# untitled.net
KiCad netlist of a schematic drawn in EAGLE
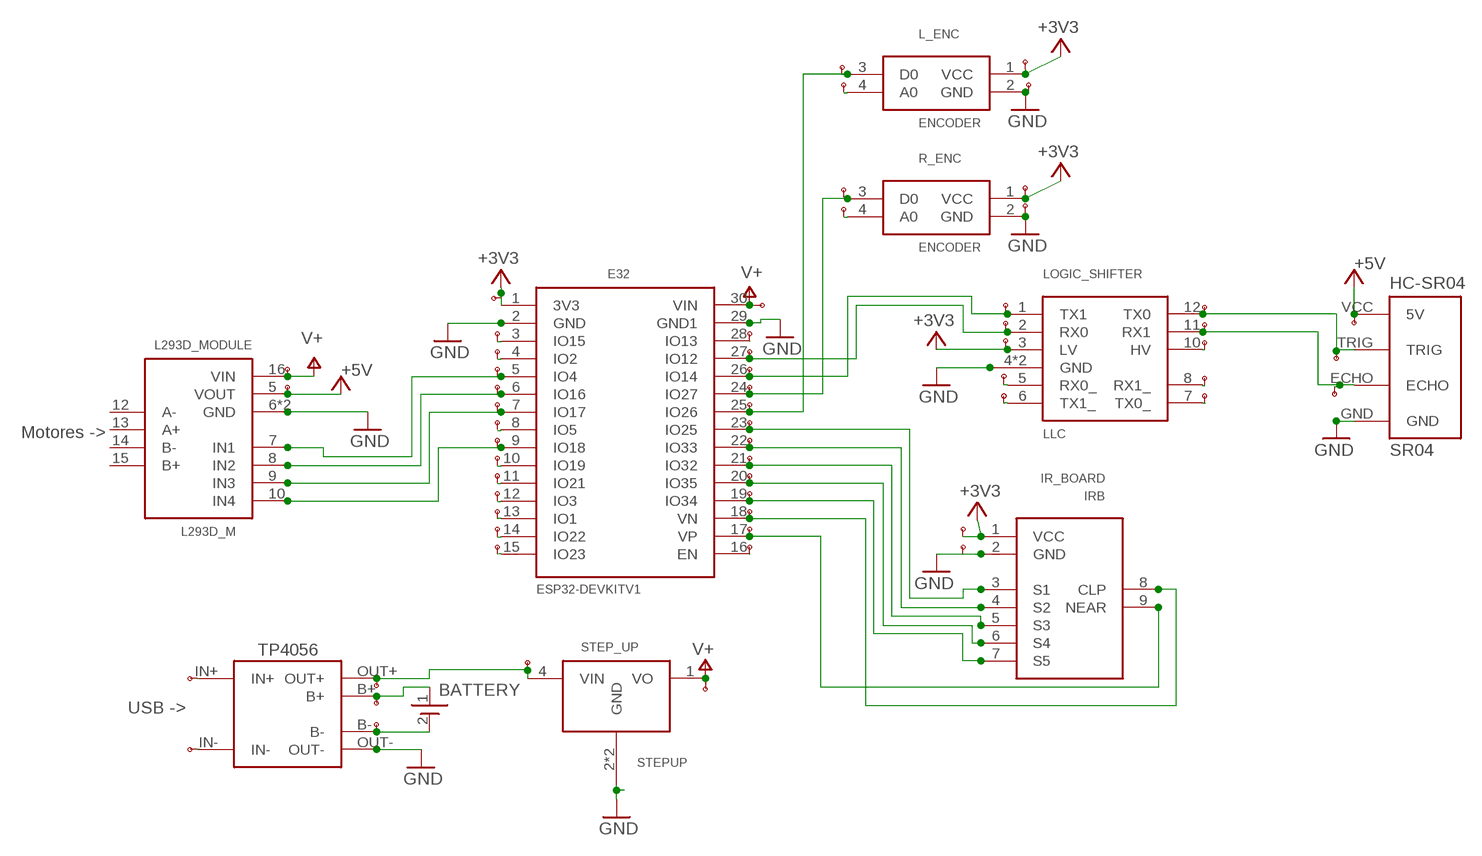
[diagram p0: schematic, sheet 1]

(export (version "E")
  (design (tool "Eeschema 10.0.6"))
  (components
    (comp (ref "BATTERY")
      (value "BAT_PAD")
      (footprint "eagle-import:BAT_PAD")
      (libsource (lib "eagle-import") (part "BAT_PAD"))
    )
    (comp (ref "BAT_CHARGER")
      (value "TP4056-MODULE")
      (footprint "eagle-import:TP4056-LITHIUM-PROTECTED-MODULE")
      (libsource (lib "eagle-import") (part "TP4056-MODULE"))
    )
    (comp (ref "E32")
      (value "ESP32DEVKITV1")
      (footprint "eagle-import:ESP32-DEVKITV1")
      (libsource (lib "eagle-import") (part "ESP32DEVKITV1"))
    )
    (comp (ref "IR_BOARD")
      (value "IRB")
      (footprint "eagle-import:IRB")
      (libsource (lib "eagle-import") (part "IRB"))
    )
    (comp (ref "L293D_MODULE")
      (value "L293D_M")
      (footprint "eagle-import:L293D_M")
      (libsource (lib "eagle-import") (part "L293D_M"))
    )
    (comp (ref "LOGIC_SHIFTER")
      (value "LLC")
      (footprint "eagle-import:LLC")
      (libsource (lib "eagle-import") (part "LLC"))
    )
    (comp (ref "L_ENC")
      (value "ENCODER")
      (footprint "eagle-import:ENCODER")
      (libsource (lib "eagle-import") (part "ENCODER"))
    )
    (comp (ref "R_ENC")
      (value "ENCODER")
      (footprint "eagle-import:ENCODER")
      (libsource (lib "eagle-import") (part "ENCODER"))
    )
    (comp (ref "SR04")
      (value "HC-SR04")
      (footprint "eagle-import:HC-SR04_FOOTPRINT")
      (libsource (lib "eagle-import") (part "HC-SR04"))
    )
    (comp (ref "STEP_UP")
      (value "STEPUP")
      (footprint "eagle-import:STEPUP")
      (libsource (lib "eagle-import") (part "STEPUP"))
    )
    (comp (ref "U$1") (value "TP") (footprint "eagle-import:TP") (libsource (lib "eagle-import") (part "TP")))
    (comp (ref "U$2") (value "TP") (footprint "eagle-import:TP") (libsource (lib "eagle-import") (part "TP")))
    (comp (ref "U$3") (value "TP") (footprint "eagle-import:TP") (libsource (lib "eagle-import") (part "TP")))
    (comp (ref "U$4") (value "TP") (footprint "eagle-import:TP") (libsource (lib "eagle-import") (part "TP")))
    (comp (ref "U$8") (value "TP") (footprint "eagle-import:TP") (libsource (lib "eagle-import") (part "TP")))
    (comp (ref "U$10")
      (value "TP")
      (footprint "eagle-import:TP")
      (libsource (lib "eagle-import") (part "TP"))
    )
    (comp (ref "U$11")
      (value "TP")
      (footprint "eagle-import:TP")
      (libsource (lib "eagle-import") (part "TP"))
    )
    (comp (ref "U$12")
      (value "TP")
      (footprint "eagle-import:TP")
      (libsource (lib "eagle-import") (part "TP"))
    )
    (comp (ref "U$13")
      (value "TP")
      (footprint "eagle-import:TP")
      (libsource (lib "eagle-import") (part "TP"))
    )
    (comp (ref "U$14")
      (value "TP")
      (footprint "eagle-import:TP")
      (libsource (lib "eagle-import") (part "TP"))
    )
    (comp (ref "U$15")
      (value "TP")
      (footprint "eagle-import:TP")
      (libsource (lib "eagle-import") (part "TP"))
    )
    (comp (ref "U$16")
      (value "TP")
      (footprint "eagle-import:TP")
      (libsource (lib "eagle-import") (part "TP"))
    )
    (comp (ref "U$17")
      (value "TP")
      (footprint "eagle-import:TP")
      (libsource (lib "eagle-import") (part "TP"))
    )
    (comp (ref "U$18")
      (value "TP")
      (footprint "eagle-import:TP")
      (libsource (lib "eagle-import") (part "TP"))
    )
    (comp (ref "U$19")
      (value "TP")
      (footprint "eagle-import:TP")
      (libsource (lib "eagle-import") (part "TP"))
    )
    (comp (ref "U$20")
      (value "TP")
      (footprint "eagle-import:TP")
      (libsource (lib "eagle-import") (part "TP"))
    )
    (comp (ref "U$21")
      (value "TP")
      (footprint "eagle-import:TP")
      (libsource (lib "eagle-import") (part "TP"))
    )
    (comp (ref "U$22")
      (value "TP")
      (footprint "eagle-import:TP")
      (libsource (lib "eagle-import") (part "TP"))
    )
    (comp (ref "U$23")
      (value "TP")
      (footprint "eagle-import:TP")
      (libsource (lib "eagle-import") (part "TP"))
    )
    (comp (ref "U$24")
      (value "TP")
      (footprint "eagle-import:TP")
      (libsource (lib "eagle-import") (part "TP"))
    )
    (comp (ref "U$25")
      (value "TP")
      (footprint "eagle-import:TP")
      (libsource (lib "eagle-import") (part "TP"))
    )
    (comp (ref "U$26")
      (value "TP")
      (footprint "eagle-import:TP")
      (libsource (lib "eagle-import") (part "TP"))
    )
    (comp (ref "U$27")
      (value "TP")
      (footprint "eagle-import:TP")
      (libsource (lib "eagle-import") (part "TP"))
    )
    (comp (ref "U$28")
      (value "TP")
      (footprint "eagle-import:TP")
      (libsource (lib "eagle-import") (part "TP"))
    )
    (comp (ref "U$29")
      (value "TP")
      (footprint "eagle-import:TP")
      (libsource (lib "eagle-import") (part "TP"))
    )
    (comp (ref "U$30")
      (value "TP")
      (footprint "eagle-import:TP")
      (libsource (lib "eagle-import") (part "TP"))
    )
    (comp (ref "U$31")
      (value "TP")
      (footprint "eagle-import:TP")
      (libsource (lib "eagle-import") (part "TP"))
    )
    (comp (ref "U$32")
      (value "TP")
      (footprint "eagle-import:TP")
      (libsource (lib "eagle-import") (part "TP"))
    )
    (comp (ref "U$33")
      (value "TP")
      (footprint "eagle-import:TP")
      (libsource (lib "eagle-import") (part "TP"))
    )
    (comp (ref "U$34")
      (value "TP")
      (footprint "eagle-import:TP")
      (libsource (lib "eagle-import") (part "TP"))
    )
    (comp (ref "U$36")
      (value "TP")
      (footprint "eagle-import:TP")
      (libsource (lib "eagle-import") (part "TP"))
    )
    (comp (ref "U$37")
      (value "TP")
      (footprint "eagle-import:TP")
      (libsource (lib "eagle-import") (part "TP"))
    )
    (comp (ref "U$38")
      (value "TP")
      (footprint "eagle-import:TP")
      (libsource (lib "eagle-import") (part "TP"))
    )
    (comp (ref "U$40")
      (value "TP")
      (footprint "eagle-import:TP")
      (libsource (lib "eagle-import") (part "TP"))
    )
    (comp (ref "U$41")
      (value "TP")
      (footprint "eagle-import:TP")
      (libsource (lib "eagle-import") (part "TP"))
    )
    (comp (ref "U$42")
      (value "TP")
      (footprint "eagle-import:TP")
      (libsource (lib "eagle-import") (part "TP"))
    )
    (comp (ref "U$43")
      (value "TP")
      (footprint "eagle-import:TP")
      (libsource (lib "eagle-import") (part "TP"))
    )
    (comp (ref "U$44")
      (value "TP")
      (footprint "eagle-import:TP")
      (libsource (lib "eagle-import") (part "TP"))
    )
    (comp (ref "U$46")
      (value "TP")
      (footprint "eagle-import:TP")
      (libsource (lib "eagle-import") (part "TP"))
    )
    (comp (ref "U$47")
      (value "TP")
      (footprint "eagle-import:TP")
      (libsource (lib "eagle-import") (part "TP"))
    )
    (comp (ref "U$48")
      (value "TP")
      (footprint "eagle-import:TP")
      (libsource (lib "eagle-import") (part "TP"))
    )
    (comp (ref "U$49")
      (value "TP")
      (footprint "eagle-import:TP")
      (libsource (lib "eagle-import") (part "TP"))
    )
    (comp (ref "U$50")
      (value "TP")
      (footprint "eagle-import:TP")
      (libsource (lib "eagle-import") (part "TP"))
    )
    (comp (ref "U$51")
      (value "TP")
      (footprint "eagle-import:TP")
      (libsource (lib "eagle-import") (part "TP"))
    )
    (comp (ref "U$52")
      (value "TP")
      (footprint "eagle-import:TP")
      (libsource (lib "eagle-import") (part "TP"))
    )
    (comp (ref "U$53")
      (value "TP")
      (footprint "eagle-import:TP")
      (libsource (lib "eagle-import") (part "TP"))
    )
    (comp (ref "U$54")
      (value "TP")
      (footprint "eagle-import:TP")
      (libsource (lib "eagle-import") (part "TP"))
    )
    (comp (ref "U$55")
      (value "TP")
      (footprint "eagle-import:TP")
      (libsource (lib "eagle-import") (part "TP"))
    )
    (comp (ref "U$56")
      (value "TP")
      (footprint "eagle-import:TP")
      (libsource (lib "eagle-import") (part "TP"))
    )
    (comp (ref "U$57")
      (value "TP")
      (footprint "eagle-import:TP")
      (libsource (lib "eagle-import") (part "TP"))
    )
    (comp (ref "U$59")
      (value "TP")
      (footprint "eagle-import:TP")
      (libsource (lib "eagle-import") (part "TP"))
    )
    (comp (ref "U$60")
      (value "TP")
      (footprint "eagle-import:TP")
      (libsource (lib "eagle-import") (part "TP"))
    )
    (comp (ref "U$61")
      (value "TP")
      (footprint "eagle-import:TP")
      (libsource (lib "eagle-import") (part "TP"))
    )
    (comp (ref "U$62")
      (value "TP")
      (footprint "eagle-import:TP")
      (libsource (lib "eagle-import") (part "TP"))
    )
    (comp (ref "U$63")
      (value "TP")
      (footprint "eagle-import:TP")
      (libsource (lib "eagle-import") (part "TP"))
    )
    (comp (ref "U$64")
      (value "TP")
      (footprint "eagle-import:TP")
      (libsource (lib "eagle-import") (part "TP"))
    )
    (comp (ref "U$65")
      (value "TP")
      (footprint "eagle-import:TP")
      (libsource (lib "eagle-import") (part "TP"))
    )
    (comp (ref "U$67")
      (value "TP")
      (footprint "eagle-import:TP")
      (libsource (lib "eagle-import") (part "TP"))
    )
    (comp (ref "U$68")
      (value "TP")
      (footprint "eagle-import:TP")
      (libsource (lib "eagle-import") (part "TP"))
    )
    (comp (ref "U$69")
      (value "TP")
      (footprint "eagle-import:TP")
      (libsource (lib "eagle-import") (part "TP"))
    )
  )
  (nets
    (net (code "1") (name "+3V3") (class "Default")
      (node (ref "E32") (pin "1") (pinfunction "3V3_1") (pintype "bidirectional"))
      (node (ref "IR_BOARD") (pin "1") (pinfunction "VCC_1") (pintype "bidirectional"))
      (node (ref "LOGIC_SHIFTER") (pin "3") (pinfunction "LV_3") (pintype "bidirectional"))
      (node (ref "L_ENC") (pin "1") (pinfunction "VCC_1") (pintype "bidirectional"))
      (node (ref "R_ENC") (pin "1") (pinfunction "VCC_1") (pintype "bidirectional"))
      (node (ref "U$3") (pin "P$1") (pinfunction "P$1_P$1") (pintype "bidirectional"))
      (node (ref "U$49") (pin "P$1") (pinfunction "P$1_P$1") (pintype "bidirectional"))
      (node (ref "U$51") (pin "P$1") (pinfunction "P$1_P$1") (pintype "bidirectional"))
      (node (ref "U$57") (pin "P$1") (pinfunction "P$1_P$1") (pintype "bidirectional"))
      (node (ref "U$8") (pin "P$1") (pinfunction "P$1_P$1") (pintype "bidirectional"))
    )
    (net (code "2") (name "+5V") (class "Default")
      (node (ref "L293D_MODULE") (pin "5") (pinfunction "VOUT_5") (pintype "output"))
      (node (ref "SR04") (pin "VCC") (pinfunction "5V_VCC") (pintype "bidirectional"))
      (node (ref "U$2") (pin "P$1") (pinfunction "P$1_P$1") (pintype "bidirectional"))
      (node (ref "U$69") (pin "P$1") (pinfunction "P$1_P$1") (pintype "bidirectional"))
    )
    (net (code "3") (name "GND") (class "Default")
      (node (ref "BAT_CHARGER") (pin "OUT-") (pinfunction "OUT-_OUT-") (pintype "power_in"))
      (node (ref "E32") (pin "2") (pinfunction "GND_2") (pintype "bidirectional"))
      (node (ref "E32") (pin "29") (pinfunction "GND1_29") (pintype "bidirectional"))
      (node (ref "IR_BOARD") (pin "2") (pinfunction "GND_2") (pintype "bidirectional"))
      (node (ref "L293D_MODULE") (pin "11") (pinfunction "GND_11") (pintype "bidirectional"))
      (node (ref "L293D_MODULE") (pin "6") (pinfunction "GND_6") (pintype "bidirectional"))
      (node (ref "LOGIC_SHIFTER") (pin "4") (pinfunction "GND_4") (pintype "bidirectional"))
      (node (ref "LOGIC_SHIFTER") (pin "9") (pinfunction "GND_9") (pintype "bidirectional"))
      (node (ref "L_ENC") (pin "2") (pinfunction "GND_2") (pintype "bidirectional"))
      (node (ref "R_ENC") (pin "2") (pinfunction "GND_2") (pintype "bidirectional"))
      (node (ref "SR04") (pin "GND") (pinfunction "GND_GND") (pintype "bidirectional"))
      (node (ref "STEP_UP") (pin "2") (pinfunction "GND_2") (pintype "bidirectional"))
      (node (ref "STEP_UP") (pin "3") (pinfunction "GND_3") (pintype "bidirectional"))
      (node (ref "U$4") (pin "P$1") (pinfunction "P$1_P$1") (pintype "bidirectional"))
      (node (ref "U$50") (pin "P$1") (pinfunction "P$1_P$1") (pintype "bidirectional"))
      (node (ref "U$52") (pin "P$1") (pinfunction "P$1_P$1") (pintype "bidirectional"))
    )
    (net (code "4") (name "Net-(BATTERY-+)") (class "Default")
      (node (ref "BATTERY") (pin "1") (pinfunction "+_1") (pintype "bidirectional"))
      (node (ref "BAT_CHARGER") (pin "B+") (pinfunction "B+_B+") (pintype "power_in"))
      (node (ref "U$41") (pin "P$1") (pinfunction "P$1_P$1") (pintype "bidirectional"))
    )
    (net (code "5") (name "Net-(BATTERY--)") (class "Default")
      (node (ref "BATTERY") (pin "2") (pinfunction "-_2") (pintype "bidirectional"))
      (node (ref "BAT_CHARGER") (pin "B-") (pinfunction "B-_B-") (pintype "power_in"))
      (node (ref "U$40") (pin "P$1") (pinfunction "P$1_P$1") (pintype "bidirectional"))
    )
    (net (code "6") (name "Net-(BAT_CHARGER-PadIN+)") (class "Default")
      (node (ref "BAT_CHARGER") (pin "IN+") (pinfunction "IN+_IN+") (pintype "power_in"))
      (node (ref "U$37") (pin "P$1") (pinfunction "P$1_P$1") (pintype "bidirectional"))
    )
    (net (code "7") (name "Net-(BAT_CHARGER-PadIN-)") (class "Default")
      (node (ref "BAT_CHARGER") (pin "IN-") (pinfunction "IN-_IN-") (pintype "power_in"))
      (node (ref "U$38") (pin "P$1") (pinfunction "P$1_P$1") (pintype "bidirectional"))
    )
    (net (code "8") (name "Net-(E32-EN)") (class "Default")
      (node (ref "E32") (pin "16") (pinfunction "EN_16") (pintype "bidirectional"))
      (node (ref "U$22") (pin "P$1") (pinfunction "P$1_P$1") (pintype "bidirectional"))
    )
    (net (code "9") (name "Net-(E32-IO1)") (class "Default")
      (node (ref "E32") (pin "13") (pinfunction "IO1_13") (pintype "bidirectional"))
      (node (ref "U$19") (pin "P$1") (pinfunction "P$1_P$1") (pintype "bidirectional"))
    )
    (net (code "10") (name "Net-(E32-IO2)") (class "Default")
      (node (ref "E32") (pin "4") (pinfunction "IO2_4") (pintype "bidirectional"))
      (node (ref "U$11") (pin "P$1") (pinfunction "P$1_P$1") (pintype "bidirectional"))
    )
    (net (code "11") (name "Net-(E32-IO3)") (class "Default")
      (node (ref "E32") (pin "12") (pinfunction "IO3_12") (pintype "bidirectional"))
      (node (ref "U$18") (pin "P$1") (pinfunction "P$1_P$1") (pintype "bidirectional"))
    )
    (net (code "12") (name "Net-(E32-IO4)") (class "Default")
      (node (ref "E32") (pin "5") (pinfunction "IO4_5") (pintype "bidirectional"))
      (node (ref "L293D_MODULE") (pin "7") (pinfunction "IN1_7") (pintype "input"))
      (node (ref "U$46") (pin "P$1") (pinfunction "P$1_P$1") (pintype "bidirectional"))
    )
    (net (code "13") (name "Net-(E32-IO5)") (class "Default")
      (node (ref "E32") (pin "8") (pinfunction "IO5_8") (pintype "bidirectional"))
      (node (ref "U$14") (pin "P$1") (pinfunction "P$1_P$1") (pintype "bidirectional"))
    )
    (net (code "14") (name "Net-(E32-IO12)") (class "Default")
      (node (ref "E32") (pin "27") (pinfunction "IO12_27") (pintype "bidirectional"))
      (node (ref "LOGIC_SHIFTER") (pin "2") (pinfunction "RX0_2") (pintype "bidirectional"))
      (node (ref "U$33") (pin "P$1") (pinfunction "P$1_P$1") (pintype "bidirectional"))
      (node (ref "U$56") (pin "P$1") (pinfunction "P$1_P$1") (pintype "bidirectional"))
    )
    (net (code "15") (name "Net-(E32-IO13)") (class "Default")
      (node (ref "E32") (pin "28") (pinfunction "IO13_28") (pintype "bidirectional"))
      (node (ref "U$34") (pin "P$1") (pinfunction "P$1_P$1") (pintype "bidirectional"))
    )
    (net (code "16") (name "Net-(E32-IO14)") (class "Default")
      (node (ref "E32") (pin "26") (pinfunction "IO14_26") (pintype "bidirectional"))
      (node (ref "LOGIC_SHIFTER") (pin "1") (pinfunction "TX1_1") (pintype "bidirectional"))
      (node (ref "U$32") (pin "P$1") (pinfunction "P$1_P$1") (pintype "bidirectional"))
      (node (ref "U$55") (pin "P$1") (pinfunction "P$1_P$1") (pintype "bidirectional"))
    )
    (net (code "17") (name "Net-(E32-IO15)") (class "Default")
      (node (ref "E32") (pin "3") (pinfunction "IO15_3") (pintype "bidirectional"))
      (node (ref "U$10") (pin "P$1") (pinfunction "P$1_P$1") (pintype "bidirectional"))
    )
    (net (code "18") (name "Net-(E32-IO16)") (class "Default")
      (node (ref "E32") (pin "6") (pinfunction "IO16_6") (pintype "bidirectional"))
      (node (ref "L293D_MODULE") (pin "8") (pinfunction "IN2_8") (pintype "input"))
      (node (ref "U$12") (pin "P$1") (pinfunction "P$1_P$1") (pintype "bidirectional"))
    )
    (net (code "19") (name "Net-(E32-IO17)") (class "Default")
      (node (ref "E32") (pin "7") (pinfunction "IO17_7") (pintype "bidirectional"))
      (node (ref "L293D_MODULE") (pin "9") (pinfunction "IN3_9") (pintype "input"))
      (node (ref "U$13") (pin "P$1") (pinfunction "P$1_P$1") (pintype "bidirectional"))
    )
    (net (code "20") (name "Net-(E32-IO18)") (class "Default")
      (node (ref "E32") (pin "9") (pinfunction "IO18_9") (pintype "bidirectional"))
      (node (ref "L293D_MODULE") (pin "10") (pinfunction "IN4_10") (pintype "input"))
      (node (ref "U$15") (pin "P$1") (pinfunction "P$1_P$1") (pintype "bidirectional"))
    )
    (net (code "21") (name "Net-(E32-IO19)") (class "Default")
      (node (ref "E32") (pin "10") (pinfunction "IO19_10") (pintype "bidirectional"))
      (node (ref "U$16") (pin "P$1") (pinfunction "P$1_P$1") (pintype "bidirectional"))
    )
    (net (code "22") (name "Net-(E32-IO21)") (class "Default")
      (node (ref "E32") (pin "11") (pinfunction "IO21_11") (pintype "bidirectional"))
      (node (ref "U$17") (pin "P$1") (pinfunction "P$1_P$1") (pintype "bidirectional"))
    )
    (net (code "23") (name "Net-(E32-IO22)") (class "Default")
      (node (ref "E32") (pin "14") (pinfunction "IO22_14") (pintype "bidirectional"))
      (node (ref "U$20") (pin "P$1") (pinfunction "P$1_P$1") (pintype "bidirectional"))
    )
    (net (code "24") (name "Net-(E32-IO23)") (class "Default")
      (node (ref "E32") (pin "15") (pinfunction "IO23_15") (pintype "bidirectional"))
      (node (ref "U$21") (pin "P$1") (pinfunction "P$1_P$1") (pintype "bidirectional"))
    )
    (net (code "25") (name "Net-(E32-IO25)") (class "Default")
      (node (ref "E32") (pin "23") (pinfunction "IO25_23") (pintype "bidirectional"))
      (node (ref "IR_BOARD") (pin "3") (pinfunction "S1_3") (pintype "bidirectional"))
      (node (ref "U$29") (pin "P$1") (pinfunction "P$1_P$1") (pintype "bidirectional"))
    )
    (net (code "26") (name "Net-(E32-IO26)") (class "Default")
      (node (ref "E32") (pin "25") (pinfunction "IO26_25") (pintype "bidirectional"))
      (node (ref "L_ENC") (pin "3") (pinfunction "D0_3") (pintype "bidirectional"))
      (node (ref "U$30") (pin "P$1") (pinfunction "P$1_P$1") (pintype "bidirectional"))
      (node (ref "U$47") (pin "P$1") (pinfunction "P$1_P$1") (pintype "bidirectional"))
    )
    (net (code "27") (name "Net-(E32-IO27)") (class "Default")
      (node (ref "E32") (pin "24") (pinfunction "IO27_24") (pintype "bidirectional"))
      (node (ref "R_ENC") (pin "3") (pinfunction "D0_3") (pintype "bidirectional"))
      (node (ref "U$31") (pin "P$1") (pinfunction "P$1_P$1") (pintype "bidirectional"))
      (node (ref "U$54") (pin "P$1") (pinfunction "P$1_P$1") (pintype "bidirectional"))
    )
    (net (code "28") (name "Net-(E32-IO32)") (class "Default")
      (node (ref "E32") (pin "21") (pinfunction "IO32_21") (pintype "bidirectional"))
      (node (ref "IR_BOARD") (pin "5") (pinfunction "S3_5") (pintype "bidirectional"))
      (node (ref "U$27") (pin "P$1") (pinfunction "P$1_P$1") (pintype "bidirectional"))
    )
    (net (code "29") (name "Net-(E32-IO33)") (class "Default")
      (node (ref "E32") (pin "22") (pinfunction "IO33_22") (pintype "bidirectional"))
      (node (ref "IR_BOARD") (pin "4") (pinfunction "S2_4") (pintype "bidirectional"))
      (node (ref "U$28") (pin "P$1") (pinfunction "P$1_P$1") (pintype "bidirectional"))
    )
    (net (code "30") (name "Net-(E32-IO34)") (class "Default")
      (node (ref "E32") (pin "19") (pinfunction "IO34_19") (pintype "bidirectional"))
      (node (ref "IR_BOARD") (pin "7") (pinfunction "S5_7") (pintype "bidirectional"))
      (node (ref "U$25") (pin "P$1") (pinfunction "P$1_P$1") (pintype "bidirectional"))
    )
    (net (code "31") (name "Net-(E32-IO35)") (class "Default")
      (node (ref "E32") (pin "20") (pinfunction "IO35_20") (pintype "bidirectional"))
      (node (ref "IR_BOARD") (pin "6") (pinfunction "S4_6") (pintype "bidirectional"))
      (node (ref "U$26") (pin "P$1") (pinfunction "P$1_P$1") (pintype "bidirectional"))
    )
    (net (code "32") (name "Net-(E32-VN)") (class "Default")
      (node (ref "E32") (pin "18") (pinfunction "VN_18") (pintype "bidirectional"))
      (node (ref "IR_BOARD") (pin "8") (pinfunction "CLP_8") (pintype "bidirectional"))
      (node (ref "U$24") (pin "P$1") (pinfunction "P$1_P$1") (pintype "bidirectional"))
    )
    (net (code "33") (name "Net-(E32-VP)") (class "Default")
      (node (ref "E32") (pin "17") (pinfunction "VP_17") (pintype "bidirectional"))
      (node (ref "IR_BOARD") (pin "9") (pinfunction "NEAR_9") (pintype "bidirectional"))
      (node (ref "U$23") (pin "P$1") (pinfunction "P$1_P$1") (pintype "bidirectional"))
    )
    (net (code "34") (name "Net-(LOGIC_SHIFTER-HV)") (class "Default")
      (node (ref "LOGIC_SHIFTER") (pin "10") (pinfunction "HV_10") (pintype "bidirectional"))
      (node (ref "U$63") (pin "P$1") (pinfunction "P$1_P$1") (pintype "bidirectional"))
    )
    (net (code "35") (name "Net-(LOGIC_SHIFTER-RX0_)") (class "Default")
      (node (ref "LOGIC_SHIFTER") (pin "5") (pinfunction "RX0__5") (pintype "bidirectional"))
      (node (ref "U$59") (pin "P$1") (pinfunction "P$1_P$1") (pintype "bidirectional"))
    )
    (net (code "36") (name "Net-(LOGIC_SHIFTER-RX1)") (class "Default")
      (node (ref "LOGIC_SHIFTER") (pin "11") (pinfunction "RX1_11") (pintype "bidirectional"))
      (node (ref "SR04") (pin "ECHO") (pinfunction "ECHO_ECHO") (pintype "bidirectional"))
      (node (ref "U$64") (pin "P$1") (pinfunction "P$1_P$1") (pintype "bidirectional"))
      (node (ref "U$67") (pin "P$1") (pinfunction "P$1_P$1") (pintype "bidirectional"))
    )
    (net (code "37") (name "Net-(LOGIC_SHIFTER-RX1_)") (class "Default")
      (node (ref "LOGIC_SHIFTER") (pin "8") (pinfunction "RX1__8") (pintype "bidirectional"))
      (node (ref "U$62") (pin "P$1") (pinfunction "P$1_P$1") (pintype "bidirectional"))
    )
    (net (code "38") (name "Net-(LOGIC_SHIFTER-TX0)") (class "Default")
      (node (ref "LOGIC_SHIFTER") (pin "12") (pinfunction "TX0_12") (pintype "bidirectional"))
      (node (ref "SR04") (pin "TRIG") (pinfunction "TRIG_TRIG") (pintype "bidirectional"))
      (node (ref "U$65") (pin "P$1") (pinfunction "P$1_P$1") (pintype "bidirectional"))
      (node (ref "U$68") (pin "P$1") (pinfunction "P$1_P$1") (pintype "bidirectional"))
    )
    (net (code "39") (name "Net-(LOGIC_SHIFTER-TX0_)") (class "Default")
      (node (ref "LOGIC_SHIFTER") (pin "7") (pinfunction "TX0__7") (pintype "bidirectional"))
      (node (ref "U$61") (pin "P$1") (pinfunction "P$1_P$1") (pintype "bidirectional"))
    )
    (net (code "40") (name "Net-(LOGIC_SHIFTER-TX1_)") (class "Default")
      (node (ref "LOGIC_SHIFTER") (pin "6") (pinfunction "TX1__6") (pintype "bidirectional"))
      (node (ref "U$60") (pin "P$1") (pinfunction "P$1_P$1") (pintype "bidirectional"))
    )
    (net (code "41") (name "Net-(L_ENC-A0)") (class "Default")
      (node (ref "L_ENC") (pin "4") (pinfunction "A0_4") (pintype "bidirectional"))
      (node (ref "U$48") (pin "P$1") (pinfunction "P$1_P$1") (pintype "bidirectional"))
    )
    (net (code "42") (name "Net-(R_ENC-A0)") (class "Default")
      (node (ref "R_ENC") (pin "4") (pinfunction "A0_4") (pintype "bidirectional"))
      (node (ref "U$53") (pin "P$1") (pinfunction "P$1_P$1") (pintype "bidirectional"))
    )
    (net (code "43") (name "Net-(STEP_UP-VIN)") (class "Default")
      (node (ref "BAT_CHARGER") (pin "OUT+") (pinfunction "OUT+_OUT+") (pintype "power_in"))
      (node (ref "STEP_UP") (pin "4") (pinfunction "VIN_4") (pintype "bidirectional"))
      (node (ref "U$42") (pin "P$1") (pinfunction "P$1_P$1") (pintype "bidirectional"))
      (node (ref "U$43") (pin "P$1") (pinfunction "P$1_P$1") (pintype "bidirectional"))
    )
    (net (code "44") (name "V+") (class "Default")
      (node (ref "E32") (pin "30") (pinfunction "VIN_30") (pintype "bidirectional"))
      (node (ref "L293D_MODULE") (pin "16") (pinfunction "VIN_16") (pintype "input"))
      (node (ref "STEP_UP") (pin "1") (pinfunction "VO_1") (pintype "bidirectional"))
      (node (ref "U$1") (pin "P$1") (pinfunction "P$1_P$1") (pintype "bidirectional"))
      (node (ref "U$36") (pin "P$1") (pinfunction "P$1_P$1") (pintype "bidirectional"))
      (node (ref "U$44") (pin "P$1") (pinfunction "P$1_P$1") (pintype "bidirectional"))
    )
    (net (code "45") (name "unconnected-(L293D_MODULE-A+-Pad13)") (class "Default")
      (node (ref "L293D_MODULE") (pin "13") (pinfunction "A+_13") (pintype "bidirectional"))
    )
    (net (code "46") (name "unconnected-(L293D_MODULE-A--Pad12)") (class "Default")
      (node (ref "L293D_MODULE") (pin "12") (pinfunction "A-_12") (pintype "bidirectional"))
    )
    (net (code "47") (name "unconnected-(L293D_MODULE-B+-Pad15)") (class "Default")
      (node (ref "L293D_MODULE") (pin "15") (pinfunction "B+_15") (pintype "bidirectional"))
    )
    (net (code "48") (name "unconnected-(L293D_MODULE-B--Pad14)") (class "Default")
      (node (ref "L293D_MODULE") (pin "14") (pinfunction "B-_14") (pintype "bidirectional"))
    )
  )
)
